# Controller_Conflict.net
KiCad netlist of a schematic drawn in Altium Designer
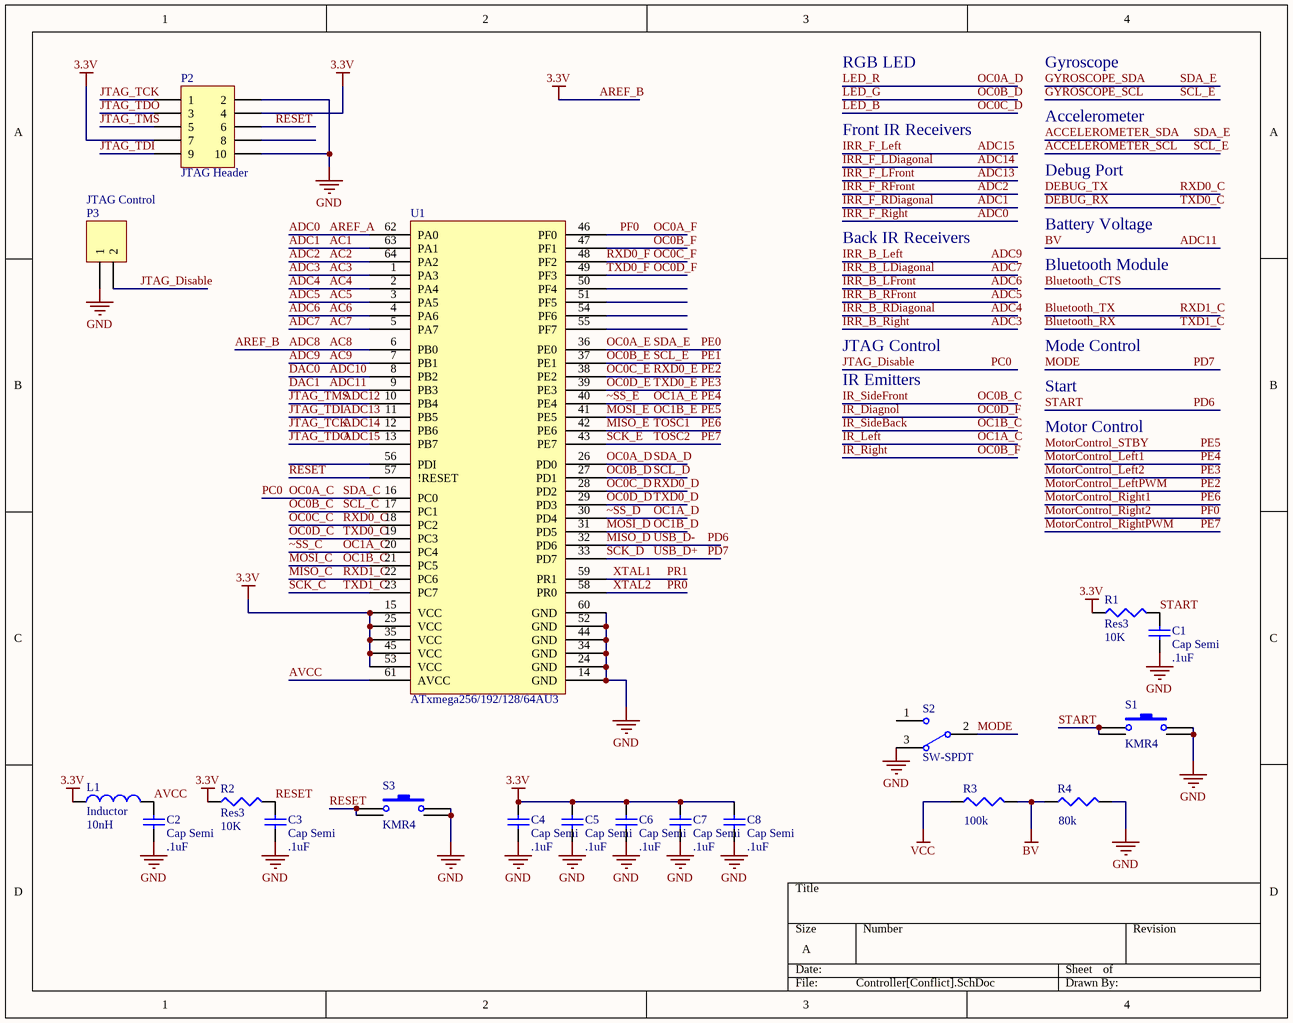
[diagram p0: Controller[Conflict].SchDoc]

(export (version "E")
  (design (tool "Eeschema 10.0.6"))
  (components
    (comp (ref "C1")
      (value "Cap Semi")
      (footprint "1608[0603]")
      (description "Capacitor (Semiconductor SIM Model)")
      (fields (field (name "ALTIUM_VALUE") ".1uF") (field (name "PUBLISHER") "Altium Limited"))
      (libsource (lib "Miscellaneous Devices") (part "Cap Semi"))
    )
    (comp (ref "C2")
      (value "Cap Semi")
      (footprint "1608[0603]")
      (description "Capacitor (Semiconductor SIM Model)")
      (fields (field (name "ALTIUM_VALUE") ".1uF") (field (name "PUBLISHER") "Altium Limited"))
      (libsource (lib "Miscellaneous Devices") (part "Cap Semi"))
    )
    (comp (ref "C3")
      (value "Cap Semi")
      (footprint "1608[0603]")
      (description "Capacitor (Semiconductor SIM Model)")
      (fields (field (name "ALTIUM_VALUE") ".1uF") (field (name "PUBLISHER") "Altium Limited"))
      (libsource (lib "Miscellaneous Devices") (part "Cap Semi"))
    )
    (comp (ref "C4")
      (value "Cap Semi")
      (footprint "1608[0603]")
      (description "Capacitor (Semiconductor SIM Model)")
      (fields (field (name "ALTIUM_VALUE") ".1uF") (field (name "PUBLISHER") "Altium Limited"))
      (libsource (lib "Miscellaneous Devices") (part "Cap Semi"))
    )
    (comp (ref "C5")
      (value "Cap Semi")
      (footprint "1608[0603]")
      (description "Capacitor (Semiconductor SIM Model)")
      (fields (field (name "ALTIUM_VALUE") ".1uF") (field (name "PUBLISHER") "Altium Limited"))
      (libsource (lib "Miscellaneous Devices") (part "Cap Semi"))
    )
    (comp (ref "C6")
      (value "Cap Semi")
      (footprint "1608[0603]")
      (description "Capacitor (Semiconductor SIM Model)")
      (fields (field (name "ALTIUM_VALUE") ".1uF") (field (name "PUBLISHER") "Altium Limited"))
      (libsource (lib "Miscellaneous Devices") (part "Cap Semi"))
    )
    (comp (ref "C7")
      (value "Cap Semi")
      (footprint "1608[0603]")
      (description "Capacitor (Semiconductor SIM Model)")
      (fields (field (name "ALTIUM_VALUE") ".1uF") (field (name "PUBLISHER") "Altium Limited"))
      (libsource (lib "Miscellaneous Devices") (part "Cap Semi"))
    )
    (comp (ref "C8")
      (value "Cap Semi")
      (footprint "1608[0603]")
      (description "Capacitor (Semiconductor SIM Model)")
      (fields (field (name "ALTIUM_VALUE") ".1uF") (field (name "PUBLISHER") "Altium Limited"))
      (libsource (lib "Miscellaneous Devices") (part "Cap Semi"))
    )
    (comp (ref "L1")
      (value "Inductor")
      (footprint "INDC1608L")
      (fields (field (name "ALTIUM_VALUE") "10nH") (field (name "PUBLISHER") "Altium Limited"))
      (libsource (lib "Miscellaneous Devices") (part "Inductor"))
    )
    (comp (ref "P2")
      (value "JTAG Header")
      (footprint "HDR2X5")
      (description "Header, 5-Pin, Dual row")
      (fields (field (name "PUBLISHER") "Altium Limited"))
      (libsource (lib "Miscellaneous Connectors") (part "Header 5X2"))
    )
    (comp (ref "P3")
      (value "JTAG Control")
      (footprint "HDR1X2")
      (description "Header, 2-Pin")
      (fields (field (name "PUBLISHER") "Altium Limited"))
      (libsource (lib "Miscellaneous Connectors") (part "Header 2"))
    )
    (comp (ref "R1")
      (value "Res3")
      (footprint "J1-0603")
      (description "Resistor")
      (fields (field (name "ALTIUM_VALUE") "10K") (field (name "PUBLISHER") "Altium Limited"))
      (libsource (lib "Miscellaneous Devices") (part "Res3"))
    )
    (comp (ref "R2")
      (value "Res3")
      (footprint "J1-0603")
      (description "Resistor")
      (fields (field (name "ALTIUM_VALUE") "10K") (field (name "PUBLISHER") "Altium Limited"))
      (libsource (lib "Miscellaneous Devices") (part "Res3"))
    )
    (comp (ref "R3")
      (value "100k")
      (footprint "J1-0603")
      (description "Resistor")
      (fields (field (name "Comment") "Res3") (field (name "PUBLISHER") "Altium Limited"))
      (libsource (lib "Miscellaneous Devices") (part "Res3"))
    )
    (comp (ref "R4")
      (value "80k")
      (footprint "J1-0603")
      (description "Resistor")
      (fields (field (name "Comment") "Res3") (field (name "PUBLISHER") "Altium Limited"))
      (libsource (lib "Miscellaneous Devices") (part "Res3"))
    )
    (comp (ref "S1")
      (value "KMR4")
      (footprint "KMR4")
      (description "Switch")
      (fields (field (name "PUBLISHER") "Altium Limited"))
      (libsource (lib "Dans_Library") (part "SPST Tactile Switch"))
    )
    (comp (ref "S2")
      (value "SW-SPDT")
      (footprint "SPDT Switch")
      (description "SPDT Subminiature Toggle Switch, Right Angle Mounting, Vertical Actuation")
      (fields (field (name "PUBLISHER") "Altium Limited"))
      (libsource (lib "SharedLibrary") (part "SW-SPDT"))
    )
    (comp (ref "S3")
      (value "KMR4")
      (footprint "KMR4")
      (description "Switch")
      (fields (field (name "PUBLISHER") "Altium Limited"))
      (libsource (lib "Dans_Library") (part "SPST Tactile Switch"))
    )
    (comp (ref "U1")
      (value "ATxmega256/192/128/64AU3")
      (footprint "TQFP80P1600X1600X120-64N")
      (libsource (lib "SharedLibrary") (part "ATxmega256/192/128/64A3U"))
    )
  )
  (nets
    (net (code "1") (name "/AC1") (class "Default")
      (node (ref "U1") (pin "63") (pinfunction "PA1_63") (pintype "passive"))
    )
    (net (code "2") (name "/AC2") (class "Default")
      (node (ref "U1") (pin "64") (pinfunction "PA2_64") (pintype "passive"))
    )
    (net (code "3") (name "/AC3") (class "Default")
      (node (ref "U1") (pin "1") (pinfunction "PA3_1") (pintype "passive"))
    )
    (net (code "4") (name "/AC4") (class "Default")
      (node (ref "U1") (pin "2") (pinfunction "PA4_2") (pintype "passive"))
    )
    (net (code "5") (name "/AC5") (class "Default")
      (node (ref "U1") (pin "3") (pinfunction "PA5_3") (pintype "passive"))
    )
    (net (code "6") (name "/AC6") (class "Default")
      (node (ref "U1") (pin "4") (pinfunction "PA6_4") (pintype "passive"))
    )
    (net (code "7") (name "/AC7") (class "Default")
      (node (ref "U1") (pin "5") (pinfunction "PA7_5") (pintype "passive"))
    )
    (net (code "8") (name "/AC9") (class "Default")
      (node (ref "U1") (pin "7") (pinfunction "PB1_7") (pintype "passive"))
    )
    (net (code "9") (name "/ACCELEROMETER_SCL") (class "Default")
      (node (ref "U1") (pin "37") (pinfunction "PE1_37") (pintype "passive"))
    )
    (net (code "10") (name "/ACCELEROMETER_SDA") (class "Default")
      (node (ref "U1") (pin "36") (pinfunction "PE0_36") (pintype "passive"))
    )
    (net (code "11") (name "/ADC0") (class "Default")
      (node (ref "U1") (pin "62") (pinfunction "PA0_62") (pintype "passive"))
    )
    (net (code "12") (name "/ADC10") (class "Default")
      (node (ref "U1") (pin "8") (pinfunction "PB2_8") (pintype "passive"))
    )
    (net (code "13") (name "/ADC12") (class "Default")
      (node (ref "P2") (pin "5") (pinfunction "5_5") (pintype "passive"))
      (node (ref "U1") (pin "10") (pinfunction "PB4_10") (pintype "passive"))
    )
    (net (code "14") (name "/ADC13") (class "Default")
      (node (ref "P2") (pin "9") (pinfunction "9_9") (pintype "passive"))
      (node (ref "U1") (pin "11") (pinfunction "PB5_11") (pintype "passive"))
    )
    (net (code "15") (name "/ADC14") (class "Default")
      (node (ref "P2") (pin "1") (pinfunction "1_1") (pintype "passive"))
      (node (ref "U1") (pin "12") (pinfunction "PB6_12") (pintype "passive"))
    )
    (net (code "16") (name "/ADC15") (class "Default")
      (node (ref "P2") (pin "3") (pinfunction "3_3") (pintype "passive"))
      (node (ref "U1") (pin "13") (pinfunction "PB7_13") (pintype "passive"))
    )
    (net (code "17") (name "/AVCC") (class "Default")
      (node (ref "C2") (pin "2") (pinfunction "2_2") (pintype "passive"))
      (node (ref "L1") (pin "2") (pinfunction "2_2") (pintype "passive"))
      (node (ref "U1") (pin "61") (pinfunction "AVCC_61") (pintype "passive"))
    )
    (net (code "19") (name "/Bluetooth_RX") (class "Default")
      (node (ref "U1") (pin "23") (pinfunction "PC7_23") (pintype "passive"))
    )
    (net (code "20") (name "/Bluetooth_TX") (class "Default")
      (node (ref "U1") (pin "22") (pinfunction "PC6_22") (pintype "passive"))
    )
    (net (code "21") (name "/DEBUG_RX") (class "Default")
      (node (ref "U1") (pin "19") (pinfunction "PC3_19") (pintype "passive"))
    )
    (net (code "22") (name "/DEBUG_TX") (class "Default")
      (node (ref "U1") (pin "18") (pinfunction "PC2_18") (pintype "passive"))
    )
    (net (code "23") (name "/IR_Diagnol") (class "Default")
      (node (ref "U1") (pin "49") (pinfunction "PF3_49") (pintype "passive"))
    )
    (net (code "24") (name "/IR_Left") (class "Default")
      (node (ref "U1") (pin "20") (pinfunction "PC4_20") (pintype "passive"))
    )
    (net (code "25") (name "/IR_Right") (class "Default")
      (node (ref "U1") (pin "47") (pinfunction "PF1_47") (pintype "passive"))
    )
    (net (code "26") (name "/IR_SideBack") (class "Default")
      (node (ref "U1") (pin "21") (pinfunction "PC5_21") (pintype "passive"))
    )
    (net (code "27") (name "/IR_SideFront") (class "Default")
      (node (ref "U1") (pin "17") (pinfunction "PC1_17") (pintype "passive"))
    )
    (net (code "28") (name "/JTAG_Disable") (class "Default")
      (node (ref "P3") (pin "2") (pinfunction "2_2") (pintype "passive"))
      (node (ref "U1") (pin "16") (pinfunction "PC0_16") (pintype "passive"))
    )
    (net (code "29") (name "/LED_B") (class "Default")
      (node (ref "U1") (pin "28") (pinfunction "PD2_28") (pintype "passive"))
    )
    (net (code "30") (name "/LED_G") (class "Default")
      (node (ref "U1") (pin "27") (pinfunction "PD1_27") (pintype "passive"))
    )
    (net (code "31") (name "/LED_R") (class "Default")
      (node (ref "U1") (pin "26") (pinfunction "PD0_26") (pintype "passive"))
    )
    (net (code "32") (name "/MISO_D") (class "Default")
      (node (ref "C1") (pin "2") (pinfunction "2_2") (pintype "passive"))
      (node (ref "R1") (pin "2") (pinfunction "2_2") (pintype "passive"))
      (node (ref "S1") (pin "1") (pinfunction "1_1") (pintype "passive"))
      (node (ref "S1") (pin "3") (pinfunction "3_3") (pintype "passive"))
      (node (ref "U1") (pin "32") (pinfunction "PD6_32") (pintype "passive"))
    )
    (net (code "33") (name "/MISO_E") (class "Default")
      (node (ref "U1") (pin "42") (pinfunction "PE6_42") (pintype "passive"))
    )
    (net (code "34") (name "/MODE") (class "Default")
      (node (ref "S2") (pin "2") (pinfunction "2_2") (pintype "passive"))
      (node (ref "U1") (pin "33") (pinfunction "PD7_33") (pintype "passive"))
    )
    (net (code "35") (name "/MOSI_D") (class "Default")
      (node (ref "U1") (pin "31") (pinfunction "PD5_31") (pintype "passive"))
    )
    (net (code "36") (name "/MOSI_E") (class "Default")
      (node (ref "U1") (pin "41") (pinfunction "PE5_41") (pintype "passive"))
    )
    (net (code "37") (name "/MotorControl_Left1") (class "Default")
      (node (ref "U1") (pin "40") (pinfunction "PE4_40") (pintype "passive"))
    )
    (net (code "38") (name "/MotorControl_Left2") (class "Default")
      (node (ref "U1") (pin "39") (pinfunction "PE3_39") (pintype "passive"))
    )
    (net (code "39") (name "/MotorControl_LeftPWM") (class "Default")
      (node (ref "U1") (pin "38") (pinfunction "PE2_38") (pintype "passive"))
    )
    (net (code "40") (name "/MotorControl_Right2") (class "Default")
      (node (ref "U1") (pin "46") (pinfunction "PF0_46") (pintype "passive"))
    )
    (net (code "41") (name "/MotorControl_RightPWM") (class "Default")
      (node (ref "U1") (pin "43") (pinfunction "PE7_43") (pintype "passive"))
    )
    (net (code "42") (name "/OC0C_F") (class "Default")
      (node (ref "U1") (pin "48") (pinfunction "PF2_48") (pintype "passive"))
    )
    (net (code "43") (name "/OC0D_D") (class "Default")
      (node (ref "U1") (pin "29") (pinfunction "PD3_29") (pintype "passive"))
    )
    (net (code "44") (name "/OC1A_D") (class "Default")
      (node (ref "U1") (pin "30") (pinfunction "PD4_30") (pintype "passive"))
    )
    (net (code "45") (name "/PR0") (class "Default")
      (node (ref "U1") (pin "58") (pinfunction "PR0_58") (pintype "passive"))
    )
    (net (code "46") (name "/PR1") (class "Default")
      (node (ref "U1") (pin "59") (pinfunction "PR1_59") (pintype "passive"))
    )
    (net (code "47") (name "/RESET") (class "Default")
      (node (ref "C3") (pin "2") (pinfunction "2_2") (pintype "passive"))
      (node (ref "P2") (pin "6") (pinfunction "6_6") (pintype "passive"))
      (node (ref "R2") (pin "2") (pinfunction "2_2") (pintype "passive"))
      (node (ref "S3") (pin "1") (pinfunction "1_1") (pintype "passive"))
      (node (ref "S3") (pin "3") (pinfunction "3_3") (pintype "passive"))
      (node (ref "U1") (pin "57") (pinfunction "!RESET_57") (pintype "passive"))
    )
    (net (code "48") (name "3.3V") (class "Default")
      (node (ref "C4") (pin "2") (pinfunction "2_2") (pintype "passive"))
      (node (ref "C5") (pin "2") (pinfunction "2_2") (pintype "passive"))
      (node (ref "C6") (pin "2") (pinfunction "2_2") (pintype "passive"))
      (node (ref "C7") (pin "2") (pinfunction "2_2") (pintype "passive"))
      (node (ref "C8") (pin "2") (pinfunction "2_2") (pintype "passive"))
      (node (ref "L1") (pin "1") (pinfunction "1_1") (pintype "passive"))
      (node (ref "P2") (pin "4") (pinfunction "4_4") (pintype "passive"))
      (node (ref "P2") (pin "7") (pinfunction "7_7") (pintype "passive"))
      (node (ref "R1") (pin "1") (pinfunction "1_1") (pintype "passive"))
      (node (ref "R2") (pin "1") (pinfunction "1_1") (pintype "passive"))
      (node (ref "U1") (pin "15") (pinfunction "VCC_15") (pintype "passive"))
      (node (ref "U1") (pin "25") (pinfunction "VCC_25") (pintype "passive"))
      (node (ref "U1") (pin "35") (pinfunction "VCC_35") (pintype "passive"))
      (node (ref "U1") (pin "45") (pinfunction "VCC_45") (pintype "passive"))
      (node (ref "U1") (pin "53") (pinfunction "VCC_53") (pintype "passive"))
      (node (ref "U1") (pin "6") (pinfunction "PB0_6") (pintype "passive"))
    )
    (net (code "49") (name "BV") (class "Default")
      (node (ref "R3") (pin "2") (pinfunction "2_2") (pintype "passive"))
      (node (ref "R4") (pin "1") (pinfunction "1_1") (pintype "passive"))
      (node (ref "U1") (pin "9") (pinfunction "PB3_9") (pintype "passive"))
    )
    (net (code "50") (name "GND") (class "Default")
      (node (ref "C1") (pin "1") (pinfunction "1_1") (pintype "passive"))
      (node (ref "C2") (pin "1") (pinfunction "1_1") (pintype "passive"))
      (node (ref "C3") (pin "1") (pinfunction "1_1") (pintype "passive"))
      (node (ref "C4") (pin "1") (pinfunction "1_1") (pintype "passive"))
      (node (ref "C5") (pin "1") (pinfunction "1_1") (pintype "passive"))
      (node (ref "C6") (pin "1") (pinfunction "1_1") (pintype "passive"))
      (node (ref "C7") (pin "1") (pinfunction "1_1") (pintype "passive"))
      (node (ref "C8") (pin "1") (pinfunction "1_1") (pintype "passive"))
      (node (ref "P2") (pin "10") (pinfunction "10_10") (pintype "passive"))
      (node (ref "P2") (pin "2") (pinfunction "2_2") (pintype "passive"))
      (node (ref "P3") (pin "1") (pinfunction "1_1") (pintype "passive"))
      (node (ref "R4") (pin "2") (pinfunction "2_2") (pintype "passive"))
      (node (ref "S1") (pin "2") (pinfunction "2_2") (pintype "passive"))
      (node (ref "S1") (pin "4") (pinfunction "4_4") (pintype "passive"))
      (node (ref "S2") (pin "3") (pinfunction "3_3") (pintype "passive"))
      (node (ref "S3") (pin "2") (pinfunction "2_2") (pintype "passive"))
      (node (ref "S3") (pin "4") (pinfunction "4_4") (pintype "passive"))
      (node (ref "U1") (pin "14") (pinfunction "GND_14") (pintype "passive"))
      (node (ref "U1") (pin "24") (pinfunction "GND_24") (pintype "passive"))
      (node (ref "U1") (pin "34") (pinfunction "GND_34") (pintype "passive"))
      (node (ref "U1") (pin "44") (pinfunction "GND_44") (pintype "passive"))
      (node (ref "U1") (pin "52") (pinfunction "GND_52") (pintype "passive"))
      (node (ref "U1") (pin "60") (pinfunction "GND_60") (pintype "passive"))
    )
    (net (code "51") (name "VCC") (class "Default")
      (node (ref "R3") (pin "1") (pinfunction "1_1") (pintype "passive"))
    )
    (net (code "52") (name "unconnected-(P2-Pad8)") (class "Default")
      (node (ref "P2") (pin "8") (pinfunction "8_8") (pintype "passive"))
    )
    (net (code "53") (name "unconnected-(S2-Pad1)") (class "Default")
      (node (ref "S2") (pin "1") (pinfunction "1_1") (pintype "passive"))
    )
    (net (code "54") (name "unconnected-(U1-PDI-Pad56)") (class "Default")
      (node (ref "U1") (pin "56") (pinfunction "PDI_56") (pintype "passive"))
    )
    (net (code "55") (name "unconnected-(U1-PF4-Pad50)") (class "Default")
      (node (ref "U1") (pin "50") (pinfunction "PF4_50") (pintype "passive"))
    )
    (net (code "56") (name "unconnected-(U1-PF5-Pad51)") (class "Default")
      (node (ref "U1") (pin "51") (pinfunction "PF5_51") (pintype "passive"))
    )
    (net (code "57") (name "unconnected-(U1-PF6-Pad54)") (class "Default")
      (node (ref "U1") (pin "54") (pinfunction "PF6_54") (pintype "passive"))
    )
    (net (code "58") (name "unconnected-(U1-PF7-Pad55)") (class "Default")
      (node (ref "U1") (pin "55") (pinfunction "PF7_55") (pintype "passive"))
    )
  )
)
